# bjt-cc.net
KiCad netlist of a schematic drawn in EAGLE
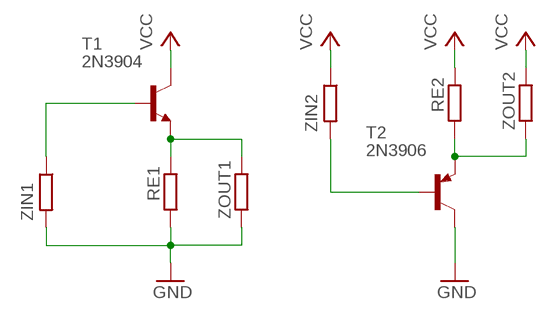
[diagram p0: schematic, sheet 1]

(export (version "E")
  (design (tool "Eeschema 10.0.6"))
  (components
    (comp (ref "RE1")
      (value "R-EU_0207/10")
      (footprint "eagle-import:0207_10")
      (libsource (lib "eagle-import") (part "R-EU_0207/10"))
    )
    (comp (ref "RE2")
      (value "R-EU_0207/10")
      (footprint "eagle-import:0207_10")
      (libsource (lib "eagle-import") (part "R-EU_0207/10"))
    )
    (comp (ref "T1")
      (value "2N3904")
      (footprint "eagle-import:TO92")
      (libsource (lib "eagle-import") (part "2N3904"))
    )
    (comp (ref "T2")
      (value "2N3906")
      (footprint "eagle-import:TO92")
      (libsource (lib "eagle-import") (part "2N3906"))
    )
    (comp (ref "ZIN1")
      (value "R-EU_0207/10")
      (footprint "eagle-import:0207_10")
      (libsource (lib "eagle-import") (part "R-EU_0207/10"))
    )
    (comp (ref "ZIN2")
      (value "R-EU_0207/10")
      (footprint "eagle-import:0207_10")
      (libsource (lib "eagle-import") (part "R-EU_0207/10"))
    )
    (comp (ref "ZOUT1")
      (value "R-EU_0207/10")
      (footprint "eagle-import:0207_10")
      (libsource (lib "eagle-import") (part "R-EU_0207/10"))
    )
    (comp (ref "ZOUT2")
      (value "R-EU_0207/10")
      (footprint "eagle-import:0207_10")
      (libsource (lib "eagle-import") (part "R-EU_0207/10"))
    )
  )
  (nets
    (net (code "1") (name "GND") (class "Default")
      (node (ref "RE1") (pin "1") (pinfunction "1_1") (pintype "passive"))
      (node (ref "T2") (pin "1") (pinfunction "C_1") (pintype "passive"))
      (node (ref "ZIN1") (pin "2") (pinfunction "2_2") (pintype "passive"))
      (node (ref "ZOUT1") (pin "1") (pinfunction "1_1") (pintype "passive"))
    )
    (net (code "2") (name "Net-(T1-B)") (class "Default")
      (node (ref "T1") (pin "2") (pinfunction "B_2") (pintype "passive"))
      (node (ref "ZIN1") (pin "1") (pinfunction "1_1") (pintype "passive"))
    )
    (net (code "3") (name "Net-(T1-E)") (class "Default")
      (node (ref "RE1") (pin "2") (pinfunction "2_2") (pintype "passive"))
      (node (ref "T1") (pin "3") (pinfunction "E_3") (pintype "passive"))
      (node (ref "ZOUT1") (pin "2") (pinfunction "2_2") (pintype "passive"))
    )
    (net (code "4") (name "Net-(T2-B)") (class "Default")
      (node (ref "T2") (pin "2") (pinfunction "B_2") (pintype "passive"))
      (node (ref "ZIN2") (pin "2") (pinfunction "2_2") (pintype "passive"))
    )
    (net (code "5") (name "Net-(T2-E)") (class "Default")
      (node (ref "RE2") (pin "1") (pinfunction "1_1") (pintype "passive"))
      (node (ref "T2") (pin "3") (pinfunction "E_3") (pintype "passive"))
      (node (ref "ZOUT2") (pin "1") (pinfunction "1_1") (pintype "passive"))
    )
    (net (code "6") (name "VCC") (class "Default")
      (node (ref "RE2") (pin "2") (pinfunction "2_2") (pintype "passive"))
      (node (ref "T1") (pin "1") (pinfunction "C_1") (pintype "passive"))
      (node (ref "ZIN2") (pin "1") (pinfunction "1_1") (pintype "passive"))
      (node (ref "ZOUT2") (pin "2") (pinfunction "2_2") (pintype "passive"))
    )
  )
)
